# ProPrj_ESP32SmartClock_2025-03-27.net
KiCad netlist of a schematic drawn in EasyEDA Pro
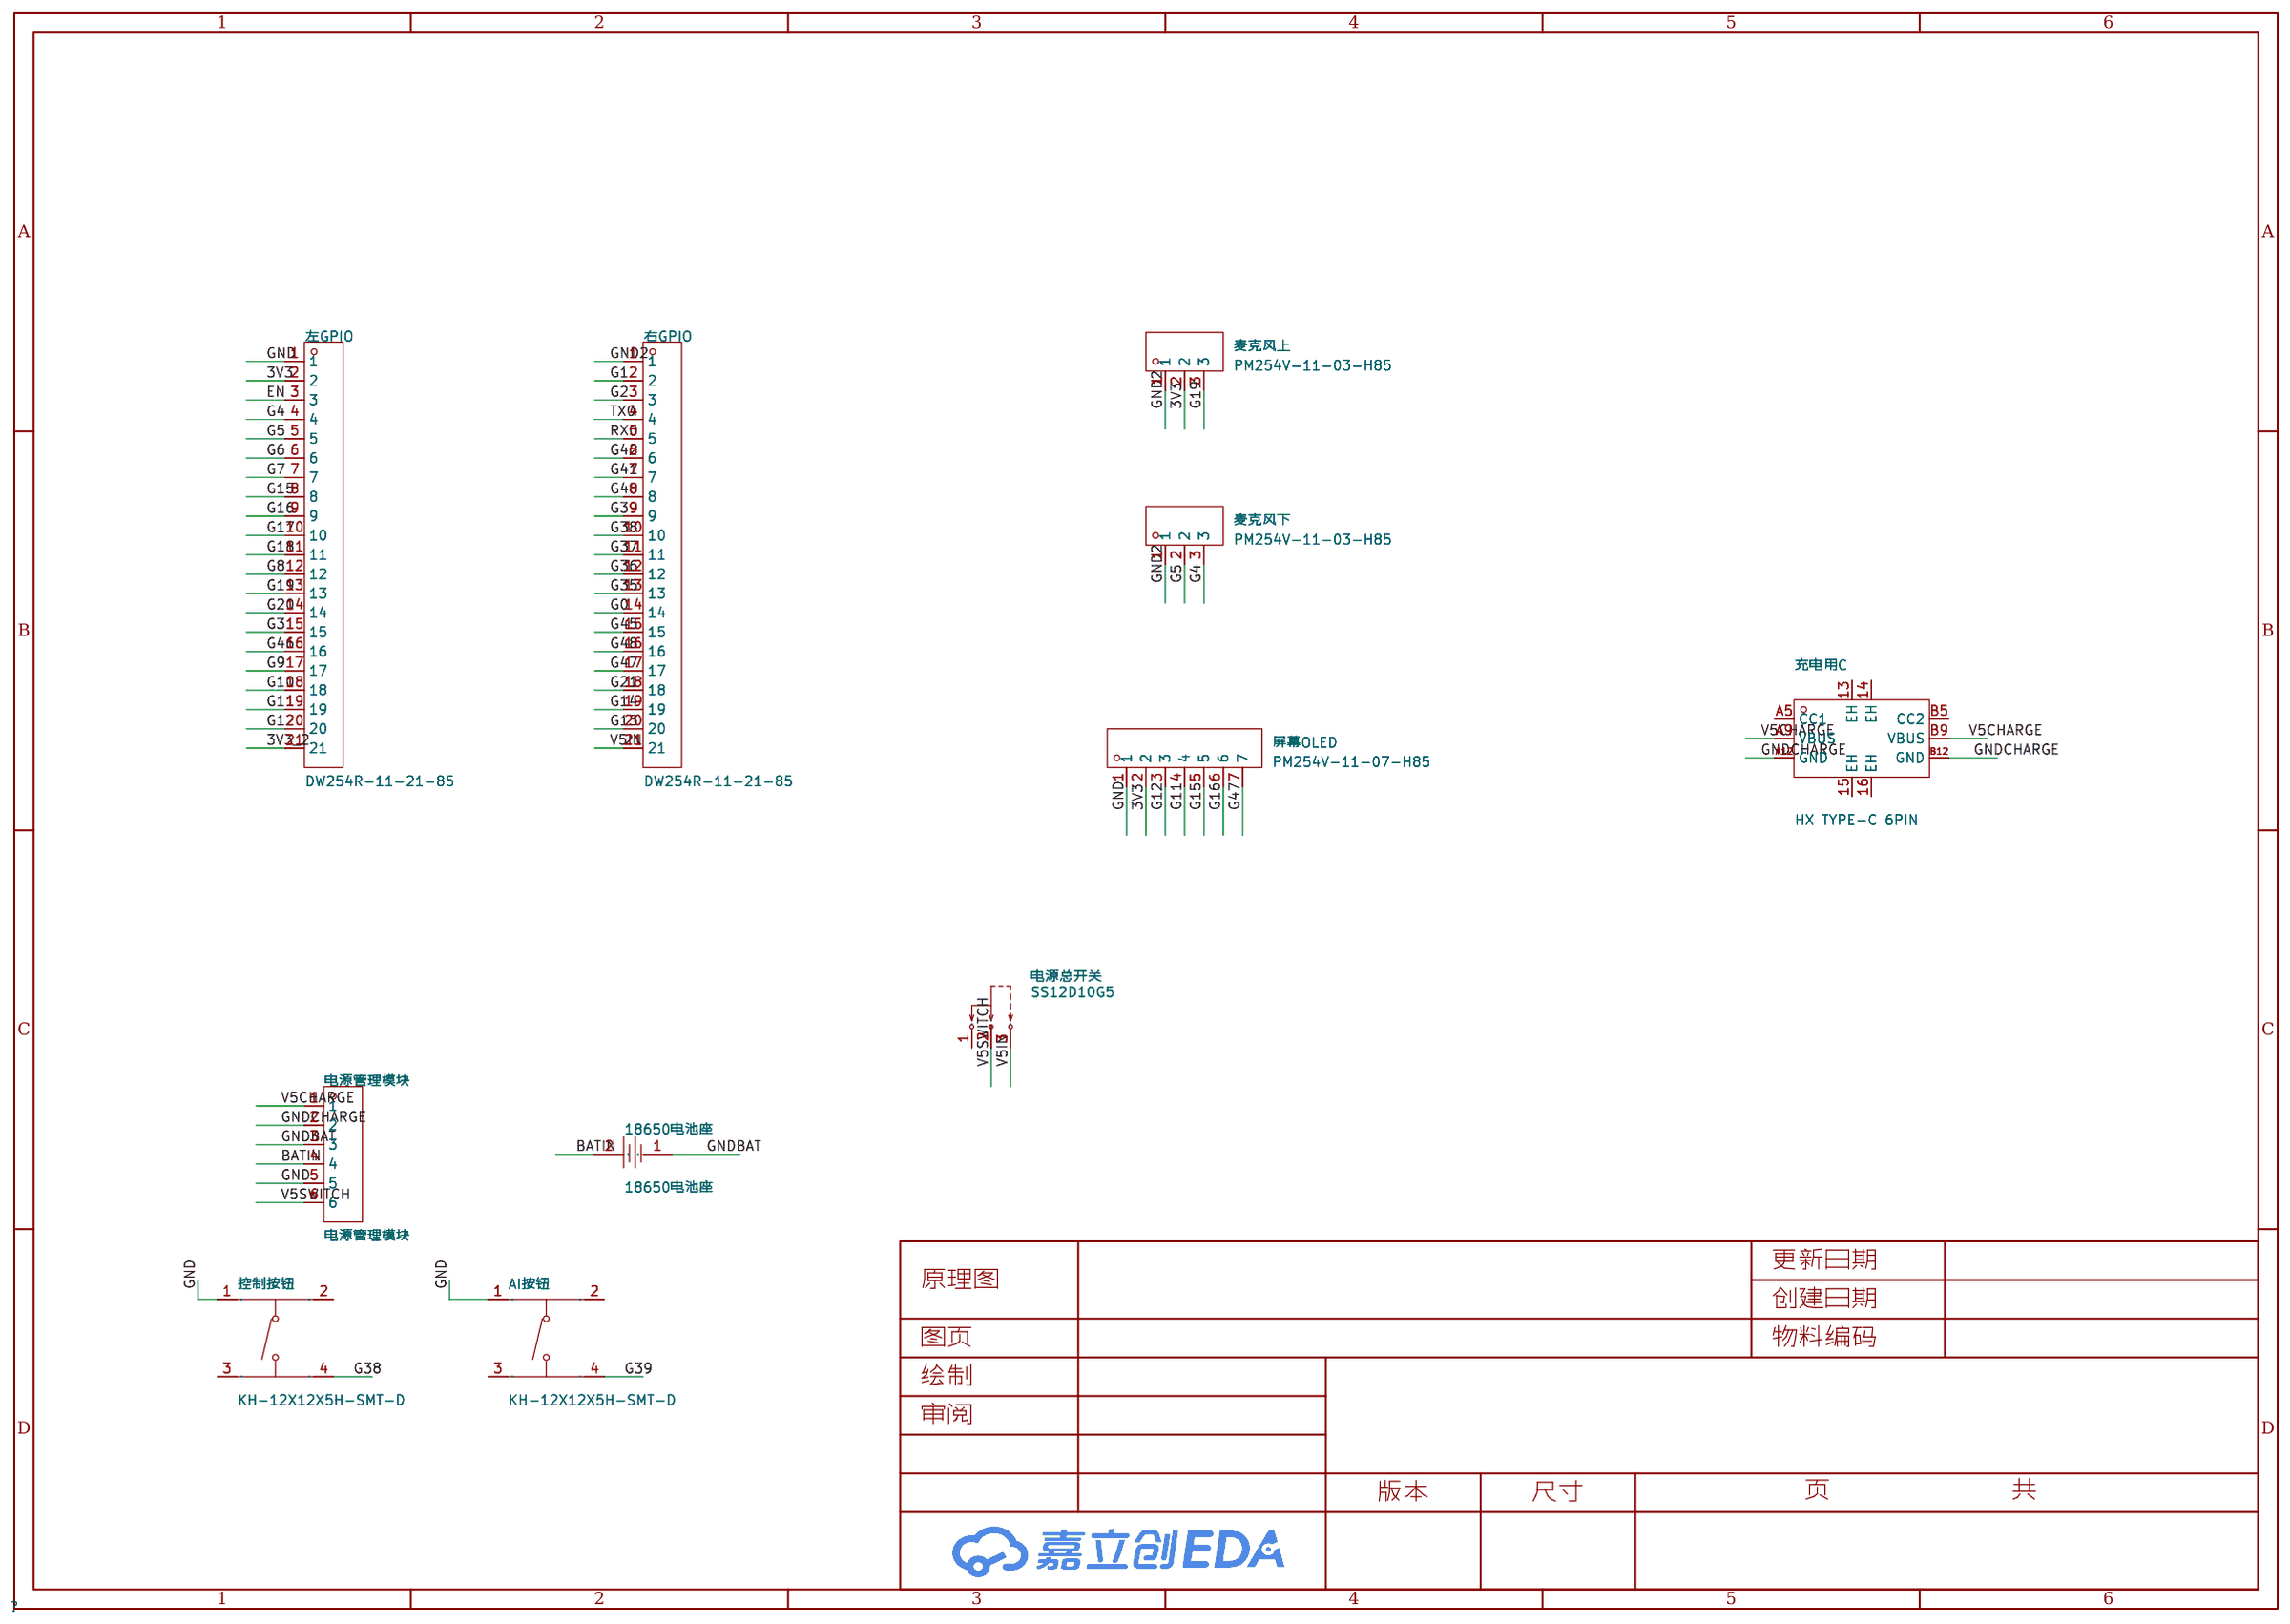
[diagram p0: schematic sheet]

(export (version "E")
  (design (tool "Eeschema 10.0.6"))
  (components
    (comp (ref "18650电池座")
      (value "18650电池座")
      (footprint "easyedapro:BATTERY-SMD_18650-1S-L77.1-W20.7-1")
      (description "连接器类型:电池盒;适用电池规格:18650;")
      (fields (field (name "Manufacturer") "MYOUNG(美阳)"))
      (libsource (lib "easyedapro") (part "BH-18650-B1BA002"))
    )
    (comp (ref "AI按钮")
      (value "KH-12X12X5H-SMT-D")
      (footprint "easyedapro:SW-SMD_4P-L12.0-W12.0-P5.00-LS15.2")
      (description "开关长度:12mm;开关宽度:12mm;开关高度:5mm;")
      (fields (field (name "Manufacturer") "kinghelm(金航标)"))
      (libsource (lib "easyedapro") (part "KH-12X12X5H-SMT-D"))
    )
    (comp (ref "充电用C")
      (value "HX TYPE-C 6PIN")
      (footprint "easyedapro:USB-C-SMD_HX-TYPE-C-6PIN")
      (description "连接器类型:Type-C;公母:母;端口数量:1;触点数量:6P;安装方式:卧贴;额定电流 - 电源:3A;工作温度范围:-25°C~+85°C;")
      (fields (field (name "Manufacturer") "hanxia(韩下)"))
      (libsource (lib "easyedapro") (part "HX TYPE-C 6PIN"))
    )
    (comp (ref "右GPIO")
      (value "DW254R-11-21-85")
      (footprint "easyedapro:HDR-TH_21P-P2.54-V-F")
      (description "插孔结构:1x21P;间距:2.54mm;安装类型:直插;排数:单排;")
      (fields (field (name "Manufacturer") "DEALON(德艺隆)"))
      (libsource (lib "easyedapro") (part "DW254R-11-21-85"))
    )
    (comp (ref "屏幕OLED")
      (value "PM254V-11-07-H85")
      (footprint "easyedapro:HDR-TH_7P-P2.54-V-F")
      (fields (field (name "Manufacturer") "XFCN(兴飞)"))
      (libsource (lib "easyedapro") (part "PM254V-11-07-H85"))
    )
    (comp (ref "左GPIO")
      (value "DW254R-11-21-85")
      (footprint "easyedapro:HDR-TH_21P-P2.54-V-F")
      (description "插孔结构:1x21P;间距:2.54mm;安装类型:直插;排数:单排;")
      (fields (field (name "Manufacturer") "DEALON(德艺隆)"))
      (libsource (lib "easyedapro") (part "DW254R-11-21-85"))
    )
    (comp (ref "控制按钮")
      (value "KH-12X12X5H-SMT-D")
      (footprint "easyedapro:SW-SMD_4P-L12.0-W12.0-P5.00-LS15.2")
      (description "开关长度:12mm;开关宽度:12mm;开关高度:5mm;")
      (fields (field (name "Manufacturer") "kinghelm(金航标)"))
      (libsource (lib "easyedapro") (part "KH-12X12X5H-SMT-D"))
    )
    (comp (ref "电源总开关")
      (value "SS12D10G5")
      (footprint "easyedapro:SW-TH_SHOU-HAN_SS12D10G4")
      (description "电路结构:单刀双掷;安装方式:直插;额定电流(DC):2A;额定电压(DC):125V;机械寿命:3千次;")
      (fields (field (name "Manufacturer") "SHOU HAN(首韩)"))
      (libsource (lib "easyedapro") (part "SS12D10G5"))
    )
    (comp (ref "电源管理模块")
      (value "电源管理模块")
      (footprint "easyedapro:HDR-TH_6P-P2.54-V-M")
      (fields (field (name "Manufacturer") "XFCN(兴飞)"))
      (libsource (lib "easyedapro") (part "PZ254V-11-06P"))
    )
    (comp (ref "麦克风上")
      (value "PM254V-11-03-H85")
      (footprint "easyedapro:HDR-TH_3P-P2.54-V-F")
      (description "插孔结构:1x3P;间距:2.54mm;行距:-;安装类型:直插;排数:单排;总孔位数:3P;塑高:-;触头材质:黄铜;触头镀层:-;")
      (fields (field (name "Manufacturer") "XFCN(兴飞)"))
      (libsource (lib "easyedapro") (part "PM254V-11-03-H85"))
    )
    (comp (ref "麦克风下")
      (value "PM254V-11-03-H85")
      (footprint "easyedapro:HDR-TH_3P-P2.54-V-F")
      (description "插孔结构:1x3P;间距:2.54mm;行距:-;安装类型:直插;排数:单排;总孔位数:3P;塑高:-;触头材质:黄铜;触头镀层:-;")
      (fields (field (name "Manufacturer") "XFCN(兴飞)"))
      (libsource (lib "easyedapro") (part "PM254V-11-03-H85"))
    )
  )
  (nets
    (net (code "1") (name "/3V3") (class "Default")
      (node (ref "屏幕OLED") (pin "2") (pinfunction "2_2") (pintype "unspecified"))
      (node (ref "左GPIO") (pin "2") (pinfunction "2_2") (pintype "unspecified"))
      (node (ref "麦克风上") (pin "2") (pinfunction "2_2") (pintype "unspecified"))
    )
    (net (code "2") (name "/3V3_2") (class "Default")
      (node (ref "左GPIO") (pin "21") (pinfunction "21_21") (pintype "unspecified"))
    )
    (net (code "3") (name "/BATIN") (class "Default")
      (node (ref "18650电池座") (pin "2") (pinfunction "2_2") (pintype "input"))
      (node (ref "电源管理模块") (pin "4") (pinfunction "4_4") (pintype "unspecified"))
    )
    (net (code "4") (name "/EN") (class "Default")
      (node (ref "左GPIO") (pin "3") (pinfunction "3_3") (pintype "unspecified"))
    )
    (net (code "5") (name "/G0") (class "Default")
      (node (ref "右GPIO") (pin "14") (pinfunction "14_14") (pintype "unspecified"))
    )
    (net (code "6") (name "/G1") (class "Default")
      (node (ref "右GPIO") (pin "2") (pinfunction "2_2") (pintype "unspecified"))
    )
    (net (code "7") (name "/G2") (class "Default")
      (node (ref "右GPIO") (pin "3") (pinfunction "3_3") (pintype "unspecified"))
    )
    (net (code "8") (name "/G3") (class "Default")
      (node (ref "左GPIO") (pin "15") (pinfunction "15_15") (pintype "unspecified"))
    )
    (net (code "9") (name "/G4") (class "Default")
      (node (ref "左GPIO") (pin "4") (pinfunction "4_4") (pintype "unspecified"))
      (node (ref "麦克风下") (pin "3") (pinfunction "3_3") (pintype "unspecified"))
    )
    (net (code "10") (name "/G5") (class "Default")
      (node (ref "左GPIO") (pin "5") (pinfunction "5_5") (pintype "unspecified"))
      (node (ref "麦克风下") (pin "2") (pinfunction "2_2") (pintype "unspecified"))
    )
    (net (code "11") (name "/G6") (class "Default")
      (node (ref "左GPIO") (pin "6") (pinfunction "6_6") (pintype "unspecified"))
    )
    (net (code "12") (name "/G7") (class "Default")
      (node (ref "左GPIO") (pin "7") (pinfunction "7_7") (pintype "unspecified"))
    )
    (net (code "13") (name "/G8") (class "Default")
      (node (ref "左GPIO") (pin "12") (pinfunction "12_12") (pintype "unspecified"))
    )
    (net (code "14") (name "/G9") (class "Default")
      (node (ref "左GPIO") (pin "17") (pinfunction "17_17") (pintype "unspecified"))
    )
    (net (code "15") (name "/G10") (class "Default")
      (node (ref "左GPIO") (pin "18") (pinfunction "18_18") (pintype "unspecified"))
    )
    (net (code "16") (name "/G11") (class "Default")
      (node (ref "屏幕OLED") (pin "4") (pinfunction "4_4") (pintype "unspecified"))
      (node (ref "左GPIO") (pin "19") (pinfunction "19_19") (pintype "unspecified"))
    )
    (net (code "17") (name "/G12") (class "Default")
      (node (ref "屏幕OLED") (pin "3") (pinfunction "3_3") (pintype "unspecified"))
      (node (ref "左GPIO") (pin "20") (pinfunction "20_20") (pintype "unspecified"))
    )
    (net (code "18") (name "/G13") (class "Default")
      (node (ref "右GPIO") (pin "20") (pinfunction "20_20") (pintype "unspecified"))
    )
    (net (code "19") (name "/G14") (class "Default")
      (node (ref "右GPIO") (pin "19") (pinfunction "19_19") (pintype "unspecified"))
    )
    (net (code "20") (name "/G15") (class "Default")
      (node (ref "屏幕OLED") (pin "5") (pinfunction "5_5") (pintype "unspecified"))
      (node (ref "左GPIO") (pin "8") (pinfunction "8_8") (pintype "unspecified"))
    )
    (net (code "21") (name "/G16") (class "Default")
      (node (ref "屏幕OLED") (pin "6") (pinfunction "6_6") (pintype "unspecified"))
      (node (ref "左GPIO") (pin "9") (pinfunction "9_9") (pintype "unspecified"))
    )
    (net (code "22") (name "/G17") (class "Default")
      (node (ref "左GPIO") (pin "10") (pinfunction "10_10") (pintype "unspecified"))
    )
    (net (code "23") (name "/G18") (class "Default")
      (node (ref "左GPIO") (pin "11") (pinfunction "11_11") (pintype "unspecified"))
    )
    (net (code "24") (name "/G19") (class "Default")
      (node (ref "左GPIO") (pin "13") (pinfunction "13_13") (pintype "unspecified"))
      (node (ref "麦克风上") (pin "3") (pinfunction "3_3") (pintype "unspecified"))
    )
    (net (code "25") (name "/G20") (class "Default")
      (node (ref "左GPIO") (pin "14") (pinfunction "14_14") (pintype "unspecified"))
    )
    (net (code "26") (name "/G21") (class "Default")
      (node (ref "右GPIO") (pin "18") (pinfunction "18_18") (pintype "unspecified"))
    )
    (net (code "27") (name "/G35") (class "Default")
      (node (ref "右GPIO") (pin "13") (pinfunction "13_13") (pintype "unspecified"))
    )
    (net (code "28") (name "/G36") (class "Default")
      (node (ref "右GPIO") (pin "12") (pinfunction "12_12") (pintype "unspecified"))
    )
    (net (code "29") (name "/G37") (class "Default")
      (node (ref "右GPIO") (pin "11") (pinfunction "11_11") (pintype "unspecified"))
    )
    (net (code "30") (name "/G38") (class "Default")
      (node (ref "右GPIO") (pin "10") (pinfunction "10_10") (pintype "unspecified"))
      (node (ref "控制按钮") (pin "4") (pinfunction "4_4") (pintype "unspecified"))
    )
    (net (code "31") (name "/G39") (class "Default")
      (node (ref "AI按钮") (pin "4") (pinfunction "4_4") (pintype "unspecified"))
      (node (ref "右GPIO") (pin "9") (pinfunction "9_9") (pintype "unspecified"))
    )
    (net (code "32") (name "/G40") (class "Default")
      (node (ref "右GPIO") (pin "8") (pinfunction "8_8") (pintype "unspecified"))
    )
    (net (code "33") (name "/G41") (class "Default")
      (node (ref "右GPIO") (pin "7") (pinfunction "7_7") (pintype "unspecified"))
    )
    (net (code "34") (name "/G42") (class "Default")
      (node (ref "右GPIO") (pin "6") (pinfunction "6_6") (pintype "unspecified"))
    )
    (net (code "35") (name "/G45") (class "Default")
      (node (ref "右GPIO") (pin "15") (pinfunction "15_15") (pintype "unspecified"))
    )
    (net (code "36") (name "/G46") (class "Default")
      (node (ref "左GPIO") (pin "16") (pinfunction "16_16") (pintype "unspecified"))
    )
    (net (code "37") (name "/G47") (class "Default")
      (node (ref "右GPIO") (pin "17") (pinfunction "17_17") (pintype "unspecified"))
      (node (ref "屏幕OLED") (pin "7") (pinfunction "7_7") (pintype "unspecified"))
    )
    (net (code "38") (name "/G48") (class "Default")
      (node (ref "右GPIO") (pin "16") (pinfunction "16_16") (pintype "unspecified"))
    )
    (net (code "39") (name "/GND") (class "Default")
      (node (ref "AI按钮") (pin "1") (pinfunction "1_1") (pintype "unspecified"))
      (node (ref "屏幕OLED") (pin "1") (pinfunction "1_1") (pintype "unspecified"))
      (node (ref "左GPIO") (pin "1") (pinfunction "1_1") (pintype "unspecified"))
      (node (ref "控制按钮") (pin "1") (pinfunction "1_1") (pintype "unspecified"))
      (node (ref "电源管理模块") (pin "5") (pinfunction "5_5") (pintype "unspecified"))
    )
    (net (code "40") (name "/GND2") (class "Default")
      (node (ref "右GPIO") (pin "1") (pinfunction "1_1") (pintype "unspecified"))
      (node (ref "麦克风上") (pin "1") (pinfunction "1_1") (pintype "unspecified"))
      (node (ref "麦克风下") (pin "1") (pinfunction "1_1") (pintype "unspecified"))
    )
    (net (code "41") (name "/GNDBAT") (class "Default")
      (node (ref "18650电池座") (pin "1") (pinfunction "1_1") (pintype "input"))
      (node (ref "电源管理模块") (pin "3") (pinfunction "3_3") (pintype "unspecified"))
    )
    (net (code "42") (name "/GNDCHARGE") (class "Default")
      (node (ref "充电用C") (pin "A12") (pinfunction "GND_A12") (pintype "unspecified"))
      (node (ref "充电用C") (pin "B12") (pinfunction "GND_B12") (pintype "unspecified"))
      (node (ref "电源管理模块") (pin "2") (pinfunction "2_2") (pintype "unspecified"))
    )
    (net (code "43") (name "/RX0") (class "Default")
      (node (ref "右GPIO") (pin "5") (pinfunction "5_5") (pintype "unspecified"))
    )
    (net (code "44") (name "/TX0") (class "Default")
      (node (ref "右GPIO") (pin "4") (pinfunction "4_4") (pintype "unspecified"))
    )
    (net (code "45") (name "/V5CHARGE") (class "Default")
      (node (ref "充电用C") (pin "A9") (pinfunction "VBUS_A9") (pintype "unspecified"))
      (node (ref "充电用C") (pin "B9") (pinfunction "VBUS_B9") (pintype "unspecified"))
      (node (ref "电源管理模块") (pin "1") (pinfunction "1_1") (pintype "unspecified"))
    )
    (net (code "46") (name "/V5IN") (class "Default")
      (node (ref "右GPIO") (pin "21") (pinfunction "21_21") (pintype "unspecified"))
      (node (ref "电源总开关") (pin "3") (pinfunction "3_3") (pintype "unspecified"))
    )
    (net (code "47") (name "/V5SWITCH") (class "Default")
      (node (ref "电源总开关") (pin "2") (pinfunction "2_2") (pintype "unspecified"))
      (node (ref "电源管理模块") (pin "6") (pinfunction "6_6") (pintype "unspecified"))
    )
    (net (code "48") (name "unconnected-(AI按钮-Pad2)") (class "Default")
      (node (ref "AI按钮") (pin "2") (pinfunction "2_2") (pintype "unspecified"))
    )
    (net (code "49") (name "unconnected-(AI按钮-Pad3)") (class "Default")
      (node (ref "AI按钮") (pin "3") (pinfunction "3_3") (pintype "unspecified"))
    )
    (net (code "50") (name "unconnected-(充电用C-CC1-PadA5)") (class "Default")
      (node (ref "充电用C") (pin "A5") (pinfunction "CC1_A5") (pintype "unspecified"))
    )
    (net (code "51") (name "unconnected-(充电用C-CC2-PadB5)") (class "Default")
      (node (ref "充电用C") (pin "B5") (pinfunction "CC2_B5") (pintype "unspecified"))
    )
    (net (code "52") (name "unconnected-(充电用C-EH-Pad13)") (class "Default")
      (node (ref "充电用C") (pin "13") (pinfunction "EH_13") (pintype "unspecified"))
    )
    (net (code "53") (name "unconnected-(充电用C-EH-Pad14)") (class "Default")
      (node (ref "充电用C") (pin "14") (pinfunction "EH_14") (pintype "unspecified"))
    )
    (net (code "54") (name "unconnected-(充电用C-EH-Pad15)") (class "Default")
      (node (ref "充电用C") (pin "15") (pinfunction "EH_15") (pintype "unspecified"))
    )
    (net (code "55") (name "unconnected-(充电用C-EH-Pad16)") (class "Default")
      (node (ref "充电用C") (pin "16") (pinfunction "EH_16") (pintype "unspecified"))
    )
    (net (code "56") (name "unconnected-(控制按钮-Pad2)") (class "Default")
      (node (ref "控制按钮") (pin "2") (pinfunction "2_2") (pintype "unspecified"))
    )
    (net (code "57") (name "unconnected-(控制按钮-Pad3)") (class "Default")
      (node (ref "控制按钮") (pin "3") (pinfunction "3_3") (pintype "unspecified"))
    )
    (net (code "58") (name "unconnected-(电源总开关-Pad1)") (class "Default")
      (node (ref "电源总开关") (pin "1") (pinfunction "1_1") (pintype "unspecified"))
    )
  )
)
